# OLM-periph-probe_ambient-boostREVB.net
KiCad netlist of a schematic drawn in EAGLE
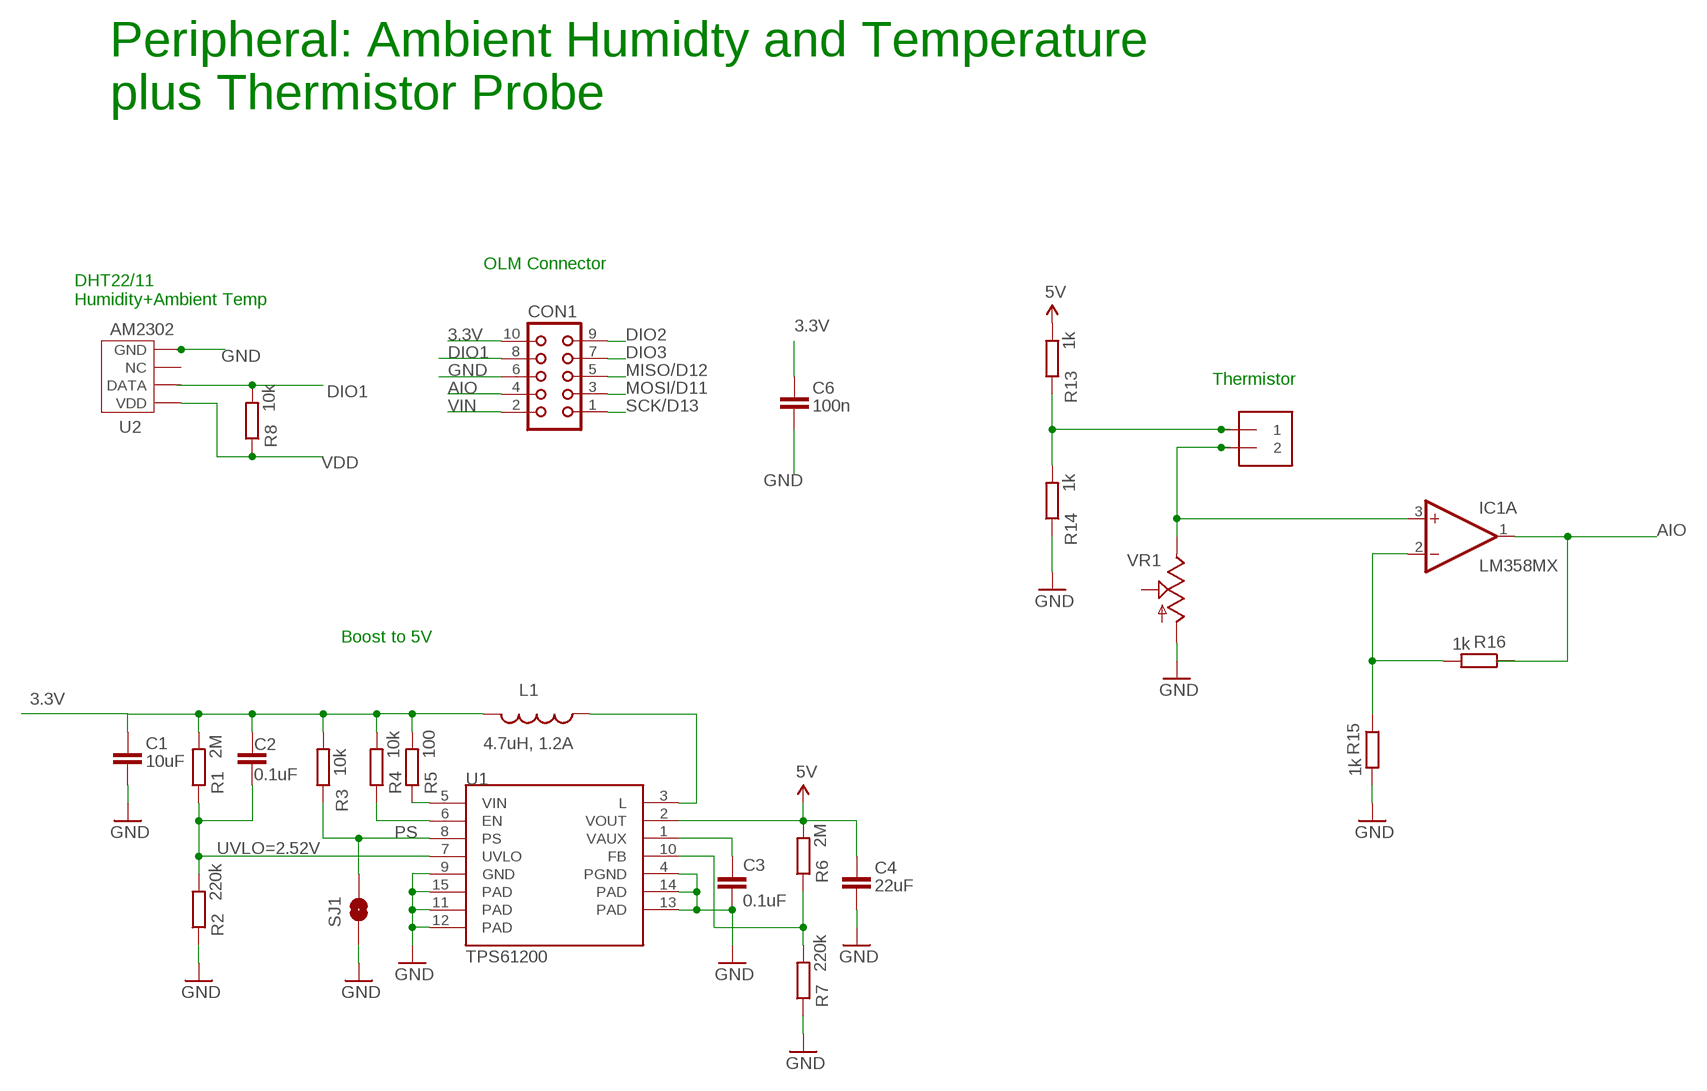
[diagram p0: schematic, sheet 1]

(export (version "E")
  (design (tool "Eeschema 10.0.6"))
  (components
    (comp (ref "C1")
      (value "10uF")
      (footprint "eagle-import:1206")
      (libsource (lib "eagle-import") (part "CAP1206"))
    )
    (comp (ref "C2")
      (value "0.1uF")
      (footprint "eagle-import:0402-CAP")
      (libsource (lib "eagle-import") (part "CAP0402-CAP"))
    )
    (comp (ref "C3")
      (value "0.1uF")
      (footprint "eagle-import:0402-CAP")
      (libsource (lib "eagle-import") (part "CAP0402-CAP"))
    )
    (comp (ref "C4")
      (value "22uF")
      (footprint "eagle-import:0805")
      (libsource (lib "eagle-import") (part "CAP0805"))
    )
    (comp (ref "C6")
      (value "100n")
      (footprint "eagle-import:0805")
      (libsource (lib "eagle-import") (part "CAP0805"))
    )
    (comp (ref "CON1")
      (value "CON10L")
      (footprint "eagle-import:CON10L")
      (libsource (lib "eagle-import") (part "CON10L"))
    )
    (comp (ref "IC1")
      (value "LM358MX")
      (footprint "eagle-import:SO08")
      (libsource (lib "eagle-import") (part "LM358MX"))
    )
    (comp (ref "J1")
      (value "1X2-3.5MM")
      (footprint "eagle-import:1X2-3.5MM")
      (libsource (lib "eagle-import") (part "1X2-3.5MM"))
    )
    (comp (ref "L1")
      (value "4.7uH, 1.2A")
      (footprint "eagle-import:CDRH2D09")
      (libsource (lib "eagle-import") (part "INDUCTOR."))
    )
    (comp (ref "R1")
      (value "2M")
      (footprint "eagle-import:R0805")
      (libsource (lib "eagle-import") (part "R-EU_R0805"))
    )
    (comp (ref "R2")
      (value "220k")
      (footprint "eagle-import:R0805")
      (libsource (lib "eagle-import") (part "R-EU_R0805"))
    )
    (comp (ref "R3")
      (value "10k")
      (footprint "eagle-import:R0805")
      (libsource (lib "eagle-import") (part "R-EU_R0805"))
    )
    (comp (ref "R4")
      (value "10k")
      (footprint "eagle-import:R0805")
      (libsource (lib "eagle-import") (part "R-EU_R0805"))
    )
    (comp (ref "R5")
      (value "100")
      (footprint "eagle-import:R0805")
      (libsource (lib "eagle-import") (part "R-EU_R0805"))
    )
    (comp (ref "R6")
      (value "2M")
      (footprint "eagle-import:R0805")
      (libsource (lib "eagle-import") (part "R-EU_R0805"))
    )
    (comp (ref "R7")
      (value "220k")
      (footprint "eagle-import:R0805")
      (libsource (lib "eagle-import") (part "R-EU_R0805"))
    )
    (comp (ref "R8")
      (value "10k")
      (footprint "eagle-import:R0805")
      (libsource (lib "eagle-import") (part "R-EU_R0805"))
    )
    (comp (ref "R13")
      (value "1k")
      (footprint "eagle-import:R0805")
      (libsource (lib "eagle-import") (part "R-EU_R0805"))
    )
    (comp (ref "R14")
      (value "1k")
      (footprint "eagle-import:R0805")
      (libsource (lib "eagle-import") (part "R-EU_R0805"))
    )
    (comp (ref "R15")
      (value "1k")
      (footprint "eagle-import:R0805")
      (libsource (lib "eagle-import") (part "R-EU_R0805"))
    )
    (comp (ref "R16")
      (value "1k")
      (footprint "eagle-import:R0805")
      (libsource (lib "eagle-import") (part "R-EU_R0805"))
    )
    (comp (ref "SJ1")
      (value "PS")
      (footprint "eagle-import:SJ_2S-NO")
      (libsource (lib "eagle-import") (part "SOLDERJUMPERNO"))
    )
    (comp (ref "U1")
      (value "TPS61200")
      (footprint "eagle-import:QFN-10_PAD")
      (libsource (lib "eagle-import") (part "TPS61200"))
    )
    (comp (ref "U2")
      (value "AM2302")
      (footprint "eagle-import:AM2302")
      (libsource (lib "eagle-import") (part "AM2302"))
    )
    (comp (ref "VR1")
      (value "10K")
      (footprint "eagle-import:ALPS_POT")
      (libsource (lib "eagle-import") (part "POT"))
    )
  )
  (nets
    (net (code "1") (name "/3.3V") (class "Default")
      (node (ref "C1") (pin "1") (pinfunction "1_1") (pintype "passive"))
      (node (ref "C2") (pin "1") (pinfunction "1_1") (pintype "passive"))
      (node (ref "C6") (pin "1") (pinfunction "1_1") (pintype "passive"))
      (node (ref "CON1") (pin "10") (pinfunction "10_10") (pintype "passive"))
      (node (ref "L1") (pin "P$2") (pinfunction "2_P$2") (pintype "passive"))
      (node (ref "R1") (pin "2") (pinfunction "2_2") (pintype "passive"))
      (node (ref "R3") (pin "2") (pinfunction "2_2") (pintype "passive"))
      (node (ref "R4") (pin "2") (pinfunction "2_2") (pintype "passive"))
      (node (ref "R5") (pin "2") (pinfunction "2_2") (pintype "passive"))
    )
    (net (code "2") (name "/AIO") (class "Default")
      (node (ref "CON1") (pin "4") (pinfunction "4_4") (pintype "passive"))
      (node (ref "IC1") (pin "1") (pinfunction "OUT_1") (pintype "output"))
      (node (ref "R16") (pin "1") (pinfunction "1_1") (pintype "passive"))
    )
    (net (code "3") (name "/DIO1") (class "Default")
      (node (ref "CON1") (pin "8") (pinfunction "8_8") (pintype "passive"))
      (node (ref "R8") (pin "2") (pinfunction "2_2") (pintype "passive"))
      (node (ref "U2") (pin "P$2") (pinfunction "DATA_P$2") (pintype "bidirectional"))
    )
    (net (code "4") (name "/DIO2") (class "Default")
      (node (ref "CON1") (pin "9") (pinfunction "9_9") (pintype "passive"))
    )
    (net (code "5") (name "/DIO3") (class "Default")
      (node (ref "CON1") (pin "7") (pinfunction "7_7") (pintype "passive"))
    )
    (net (code "6") (name "/MISO{slash}D12") (class "Default")
      (node (ref "CON1") (pin "5") (pinfunction "5_5") (pintype "passive"))
    )
    (net (code "7") (name "/MOSI{slash}D11") (class "Default")
      (node (ref "CON1") (pin "3") (pinfunction "3_3") (pintype "passive"))
    )
    (net (code "8") (name "/PS") (class "Default")
      (node (ref "R3") (pin "1") (pinfunction "1_1") (pintype "passive"))
      (node (ref "SJ1") (pin "2") (pinfunction "2_2") (pintype "passive"))
      (node (ref "U1") (pin "8") (pinfunction "PS_8") (pintype "input"))
    )
    (net (code "9") (name "/SCK{slash}D13") (class "Default")
      (node (ref "CON1") (pin "1") (pinfunction "1_1") (pintype "passive"))
    )
    (net (code "10") (name "/VDD") (class "Default")
      (node (ref "R8") (pin "1") (pinfunction "1_1") (pintype "passive"))
      (node (ref "U2") (pin "P$1") (pinfunction "VDD_P$1") (pintype "power_in"))
    )
    (net (code "11") (name "/VIN") (class "Default")
      (node (ref "CON1") (pin "2") (pinfunction "2_2") (pintype "passive"))
    )
    (net (code "12") (name "5V") (class "Default")
      (node (ref "C4") (pin "1") (pinfunction "1_1") (pintype "passive"))
      (node (ref "R13") (pin "2") (pinfunction "2_2") (pintype "passive"))
      (node (ref "R6") (pin "2") (pinfunction "2_2") (pintype "passive"))
      (node (ref "U1") (pin "2") (pinfunction "VOUT_2") (pintype "passive"))
    )
    (net (code "13") (name "GND") (class "Default")
      (node (ref "C1") (pin "2") (pinfunction "2_2") (pintype "passive"))
      (node (ref "C3") (pin "2") (pinfunction "2_2") (pintype "passive"))
      (node (ref "C4") (pin "2") (pinfunction "2_2") (pintype "passive"))
      (node (ref "C6") (pin "2") (pinfunction "2_2") (pintype "passive"))
      (node (ref "CON1") (pin "6") (pinfunction "6_6") (pintype "passive"))
      (node (ref "R14") (pin "1") (pinfunction "1_1") (pintype "passive"))
      (node (ref "R15") (pin "2") (pinfunction "2_2") (pintype "passive"))
      (node (ref "R2") (pin "1") (pinfunction "1_1") (pintype "passive"))
      (node (ref "R7") (pin "1") (pinfunction "1_1") (pintype "passive"))
      (node (ref "SJ1") (pin "1") (pinfunction "1_1") (pintype "passive"))
      (node (ref "U1") (pin "11") (pinfunction "PAD_11") (pintype "power_in"))
      (node (ref "U1") (pin "12") (pinfunction "PAD_12") (pintype "power_in"))
      (node (ref "U1") (pin "13") (pinfunction "PAD_13") (pintype "power_in"))
      (node (ref "U1") (pin "14") (pinfunction "PAD_14") (pintype "power_in"))
      (node (ref "U1") (pin "15") (pinfunction "PAD_15") (pintype "power_in"))
      (node (ref "U1") (pin "4") (pinfunction "PGND_4") (pintype "power_in"))
      (node (ref "U1") (pin "9") (pinfunction "GND_9") (pintype "power_in"))
      (node (ref "U2") (pin "P$4") (pinfunction "GND_P$4") (pintype "power_in"))
      (node (ref "VR1") (pin "P$3") (pinfunction "A_P$3") (pintype "passive"))
    )
    (net (code "14") (name "Net-(IC1A-+IN)") (class "Default")
      (node (ref "IC1") (pin "3") (pinfunction "+IN_3") (pintype "input"))
      (node (ref "J1") (pin "2") (pinfunction "2_2") (pintype "passive"))
      (node (ref "VR1") (pin "P$1") (pinfunction "E_P$1") (pintype "passive"))
    )
    (net (code "15") (name "Net-(IC1A--IN)") (class "Default")
      (node (ref "IC1") (pin "2") (pinfunction "-IN_2") (pintype "input"))
      (node (ref "R15") (pin "1") (pinfunction "1_1") (pintype "passive"))
      (node (ref "R16") (pin "2") (pinfunction "2_2") (pintype "passive"))
    )
    (net (code "16") (name "Net-(J1-Pad1)") (class "Default")
      (node (ref "J1") (pin "1") (pinfunction "1_1") (pintype "passive"))
      (node (ref "R13") (pin "1") (pinfunction "1_1") (pintype "passive"))
      (node (ref "R14") (pin "2") (pinfunction "2_2") (pintype "passive"))
    )
    (net (code "17") (name "Net-(L1-1)") (class "Default")
      (node (ref "L1") (pin "P$1") (pinfunction "1_P$1") (pintype "passive"))
      (node (ref "U1") (pin "3") (pinfunction "L_3") (pintype "passive"))
    )
    (net (code "18") (name "Net-(U1-EN)") (class "Default")
      (node (ref "R4") (pin "1") (pinfunction "1_1") (pintype "passive"))
      (node (ref "U1") (pin "6") (pinfunction "EN_6") (pintype "input"))
    )
    (net (code "19") (name "Net-(U1-FB)") (class "Default")
      (node (ref "R6") (pin "1") (pinfunction "1_1") (pintype "passive"))
      (node (ref "R7") (pin "2") (pinfunction "2_2") (pintype "passive"))
      (node (ref "U1") (pin "10") (pinfunction "FB_10") (pintype "passive"))
    )
    (net (code "20") (name "Net-(U1-UVLO)") (class "Default")
      (node (ref "C2") (pin "2") (pinfunction "2_2") (pintype "passive"))
      (node (ref "R1") (pin "1") (pinfunction "1_1") (pintype "passive"))
      (node (ref "R2") (pin "2") (pinfunction "2_2") (pintype "passive"))
      (node (ref "U1") (pin "7") (pinfunction "UVLO_7") (pintype "passive"))
    )
    (net (code "21") (name "Net-(U1-VAUX)") (class "Default")
      (node (ref "C3") (pin "1") (pinfunction "1_1") (pintype "passive"))
      (node (ref "U1") (pin "1") (pinfunction "VAUX_1") (pintype "passive"))
    )
    (net (code "22") (name "Net-(U1-VIN)") (class "Default")
      (node (ref "R5") (pin "1") (pinfunction "1_1") (pintype "passive"))
      (node (ref "U1") (pin "5") (pinfunction "VIN_5") (pintype "power_in"))
    )
    (net (code "23") (name "unconnected-(U2-NC-PadP$3)") (class "Default")
      (node (ref "U2") (pin "P$3") (pinfunction "NC_P$3") (pintype "no_connect"))
    )
    (net (code "24") (name "unconnected-(VR1-S-PadP$2)") (class "Default")
      (node (ref "VR1") (pin "P$2") (pinfunction "S_P$2") (pintype "passive"))
    )
  )
)
